# ColdRaskroj.net
KiCad netlist of a schematic drawn in EAGLE
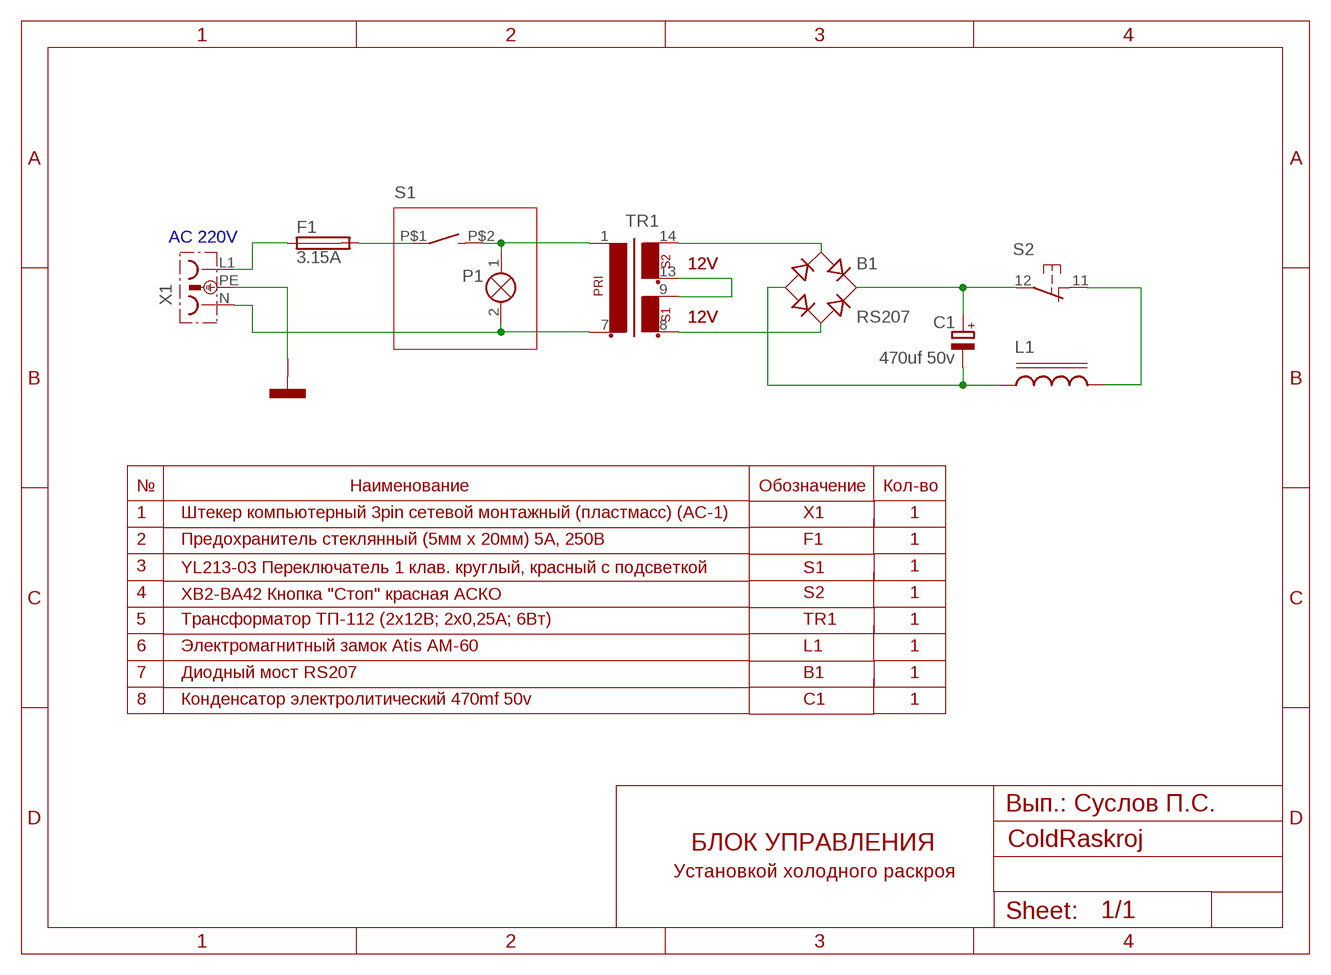
[diagram p0: schematic, sheet 1]

(export (version "E")
  (design (tool "Eeschema 10.0.6"))
  (components
    (comp (ref "B1")
      (value "RS207")
      (footprint "eagle-import:B-DIL")
      (libsource (lib "eagle-import") (part "B-DIL"))
    )
    (comp (ref "C1")
      (value "470uf 50v")
      (footprint "eagle-import:085CS_1AR")
      (libsource (lib "eagle-import") (part "CPOL-EU085CS-1AR"))
    )
    (comp (ref "F1")
      (value "3.15A")
      (footprint "eagle-import:GSH15")
      (fields (field (name "MPN") "64900001039"))
      (libsource (lib "eagle-import") (part "GSH15"))
    )
    (comp (ref "GG")
      (value "MASSE_ALLGEMEIN")
      (footprint "eagle-import:MASSE_ALLGEMEIN")
      (libsource (lib "eagle-import") (part "MASSE_ALLGEMEIN"))
    )
    (comp (ref "L1")
      (value "L-US0204/5")
      (footprint "eagle-import:0204_5")
      (libsource (lib "eagle-import") (part "L-US0204/5"))
    )
    (comp (ref "P1")
      (value "SIGNALLAMPE")
      (footprint "eagle-import:LAMPE")
      (libsource (lib "eagle-import") (part "SIGNALLAMPE"))
    )
    (comp (ref "S1")
      (value "SCHLIESSER_ARBEITSKONTAKT")
      (footprint "eagle-import:1")
      (libsource (lib "eagle-import") (part "SCHLIESSER_ARBEITSKONTAKT"))
    )
    (comp (ref "S2")
      (value "OEFFNER_TASTSCHALTER")
      (footprint "eagle-import:OEFFNER_TASTSCHALTER")
      (libsource (lib "eagle-import") (part "OEFFNER_TASTSCHALTER"))
    )
    (comp (ref "TR1")
      (value "BV054-5387.0K")
      (footprint "eagle-import:EI54-18,8_16VA")
      (libsource (lib "eagle-import") (part "BV054-5387.0K"))
    )
    (comp (ref "X1")
      (value "STECKDOSE")
      (footprint "eagle-import:STECKDOSE")
      (libsource (lib "eagle-import") (part "STECKDOSE"))
    )
  )
  (nets
    (net (code "1") (name "Net-(B1-Pad-)") (class "Default")
      (node (ref "B1") (pin "-") (pinfunction "-_-") (pintype "passive"))
      (node (ref "C1") (pin "-") (pinfunction "-_-") (pintype "passive"))
      (node (ref "L1") (pin "1") (pinfunction "1_1") (pintype "passive"))
    )
    (net (code "2") (name "Net-(F1-Pad1)") (class "Default")
      (node (ref "F1") (pin "1") (pinfunction "1_1") (pintype "passive"))
      (node (ref "X1") (pin "L1") (pinfunction "L1_L1") (pintype "passive"))
    )
    (net (code "3") (name "Net-(GG-0V)") (class "Default")
      (node (ref "GG") (pin "1") (pinfunction "0V_1") (pintype "passive"))
      (node (ref "X1") (pin "PE") (pinfunction "PE_PE") (pintype "passive"))
    )
    (net (code "4") (name "Net-(P1-X1)") (class "Default")
      (node (ref "P1") (pin "1") (pinfunction "X1_1") (pintype "passive"))
      (node (ref "S1") (pin "P$2") (pinfunction "3_P$2") (pintype "passive"))
      (node (ref "TR1") (pin "1") (pinfunction "1_1") (pintype "passive"))
    )
    (net (code "5") (name "Net-(P1-X2)") (class "Default")
      (node (ref "P1") (pin "2") (pinfunction "X2_2") (pintype "passive"))
      (node (ref "TR1") (pin "7") (pinfunction "2_7") (pintype "passive"))
      (node (ref "X1") (pin "N") (pinfunction "N_N") (pintype "passive"))
    )
    (net (code "6") (name "Net-(S1-4)") (class "Default")
      (node (ref "F1") (pin "2") (pinfunction "2_2") (pintype "passive"))
      (node (ref "S1") (pin "P$1") (pinfunction "4_P$1") (pintype "passive"))
    )
    (net (code "7") (name "Net-(S2-1)") (class "Default")
      (node (ref "L1") (pin "2") (pinfunction "2_2") (pintype "passive"))
      (node (ref "S2") (pin "11") (pinfunction "1_11") (pintype "input"))
    )
    (net (code "8") (name "Net-(S2-2)") (class "Default")
      (node (ref "B1") (pin "+") (pinfunction "+_+") (pintype "passive"))
      (node (ref "C1") (pin "+") (pinfunction "+_+") (pintype "passive"))
      (node (ref "S2") (pin "12") (pinfunction "2_12") (pintype "input"))
    )
    (net (code "9") (name "Net-(TR1-3)") (class "Default")
      (node (ref "B1") (pin "AC2") (pinfunction "AC2_AC2") (pintype "passive"))
      (node (ref "TR1") (pin "8") (pinfunction "3_8") (pintype "passive"))
    )
    (net (code "10") (name "Net-(TR1-4)") (class "Default")
      (node (ref "TR1") (pin "13") (pinfunction "5_13") (pintype "passive"))
      (node (ref "TR1") (pin "9") (pinfunction "4_9") (pintype "passive"))
    )
    (net (code "11") (name "Net-(TR1-6)") (class "Default")
      (node (ref "B1") (pin "AC1") (pinfunction "AC1_AC1") (pintype "passive"))
      (node (ref "TR1") (pin "14") (pinfunction "6_14") (pintype "passive"))
    )
  )
)
